# Bluetooth_Mate_4_0.net
KiCad netlist of a schematic drawn in EAGLE
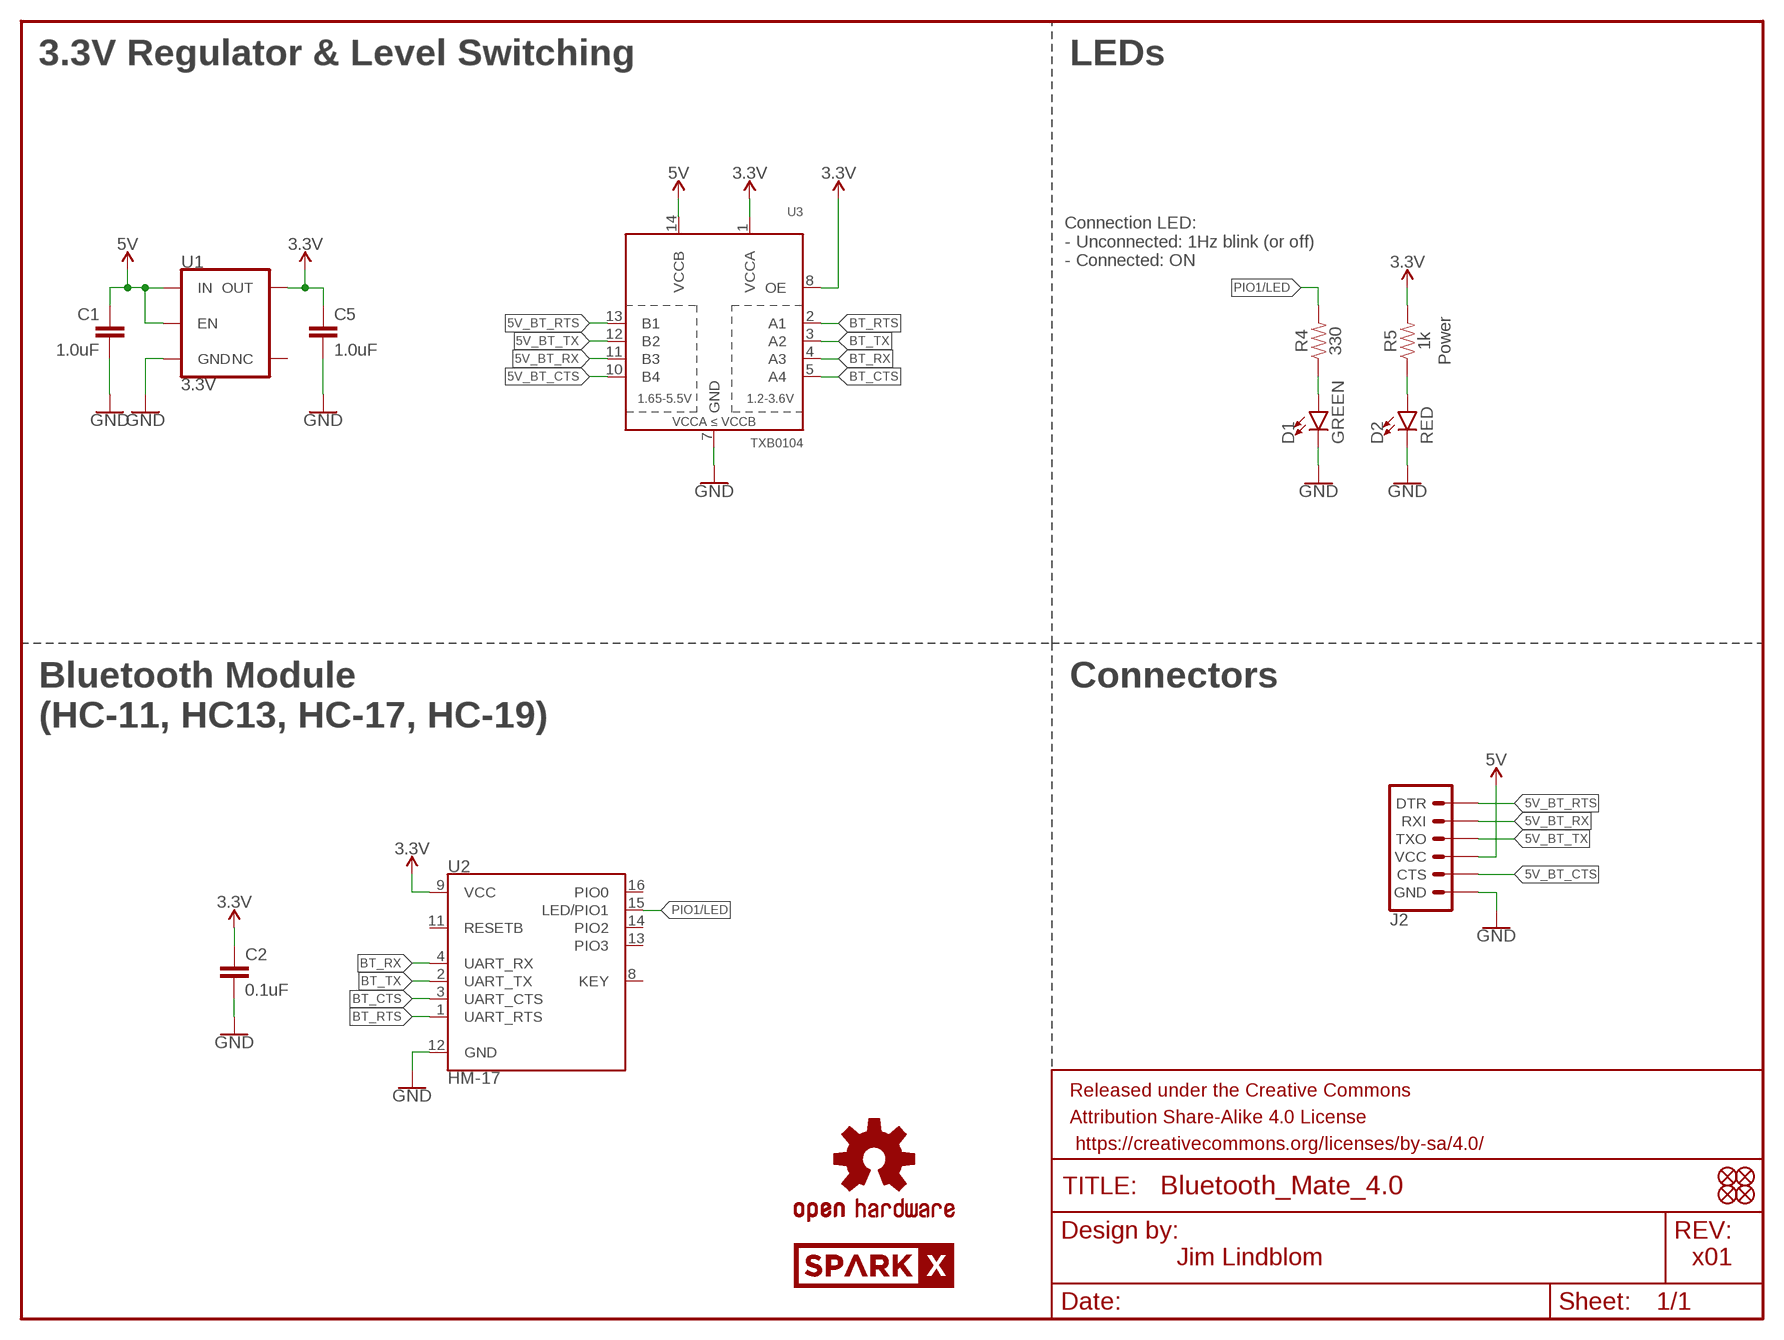
[diagram p0: schematic, sheet 1]

(export (version "E")
  (design (tool "Eeschema 10.0.6"))
  (components
    (comp (ref "C1")
      (value "1.0uF")
      (footprint "eagle-import:0603")
      (libsource (lib "eagle-import") (part "1.0UF-0603-16V-10%"))
    )
    (comp (ref "C2")
      (value "0.1uF")
      (footprint "eagle-import:0603")
      (libsource (lib "eagle-import") (part "0.1UF-0603-25V-(+80/-20%)"))
    )
    (comp (ref "C5")
      (value "1.0uF")
      (footprint "eagle-import:0603")
      (libsource (lib "eagle-import") (part "1.0UF-0603-16V-10%"))
    )
    (comp (ref "D1")
      (value "GREEN")
      (footprint "eagle-import:LED-0603")
      (libsource (lib "eagle-import") (part "LED-GREEN0603"))
    )
    (comp (ref "D2")
      (value "RED")
      (footprint "eagle-import:LED-0603")
      (libsource (lib "eagle-import") (part "LED-RED0603"))
    )
    (comp (ref "FD1")
      (value "FIDUCIALUFIDUCIAL")
      (footprint "eagle-import:FIDUCIAL-MICRO")
      (libsource (lib "eagle-import") (part "FIDUCIALUFIDUCIAL"))
    )
    (comp (ref "FD2")
      (value "FIDUCIALUFIDUCIAL")
      (footprint "eagle-import:FIDUCIAL-MICRO")
      (libsource (lib "eagle-import") (part "FIDUCIALUFIDUCIAL"))
    )
    (comp (ref "FD3")
      (value "FIDUCIALUFIDUCIAL")
      (footprint "eagle-import:FIDUCIAL-MICRO")
      (libsource (lib "eagle-import") (part "FIDUCIALUFIDUCIAL"))
    )
    (comp (ref "FD4")
      (value "FIDUCIALUFIDUCIAL")
      (footprint "eagle-import:FIDUCIAL-MICRO")
      (libsource (lib "eagle-import") (part "FIDUCIALUFIDUCIAL"))
    )
    (comp (ref "FRAME1")
      (value "FRAME-LETTER")
      (footprint "eagle-import:CREATIVE_COMMONS")
      (libsource (lib "eagle-import") (part "FRAME-LETTER"))
    )
    (comp (ref "J2")
      (value "6_PIN_SERIAL_TARGETNO_SILK")
      (footprint "eagle-import:1X06_NO_SILK")
      (libsource (lib "eagle-import") (part "6_PIN_SERIAL_TARGETNO_SILK"))
    )
    (comp (ref "LOGO1")
      (value "OSHW-LOGOMINI")
      (footprint "eagle-import:OSHW-LOGO-MINI")
      (libsource (lib "eagle-import") (part "OSHW-LOGOMINI"))
    )
    (comp (ref "LOGO3")
      (value "SPARKX-LOGO5")
      (footprint "eagle-import:SPARKX-LARGE")
      (libsource (lib "eagle-import") (part "SPARKX-LOGO5"))
    )
    (comp (ref "R4")
      (value "330")
      (footprint "eagle-import:0603")
      (libsource (lib "eagle-import") (part "330OHM-0603-1/10W-1%"))
    )
    (comp (ref "R5")
      (value "1k")
      (footprint "eagle-import:0603")
      (libsource (lib "eagle-import") (part "1KOHM-0603-1/10W-1%"))
    )
    (comp (ref "U1")
      (value "3.3V")
      (footprint "eagle-import:SOT23-5")
      (libsource (lib "eagle-import") (part "V_REG_AP2112K-3.3V"))
    )
    (comp (ref "U2")
      (value "HM-17")
      (footprint "eagle-import:HM-11")
      (libsource (lib "eagle-import") (part "HM-17"))
    )
    (comp (ref "U3")
      (value "TXB0104")
      (footprint "eagle-import:TSSOP14")
      (libsource (lib "eagle-import") (part "TXB0104PWR"))
    )
  )
  (nets
    (net (code "1") (name "3.3V") (class "Default")
      (node (ref "C2") (pin "1") (pinfunction "1_1") (pintype "passive"))
      (node (ref "C5") (pin "1") (pinfunction "1_1") (pintype "passive"))
      (node (ref "R5") (pin "2") (pinfunction "2_2") (pintype "passive"))
      (node (ref "U1") (pin "5") (pinfunction "OUT_5") (pintype "passive"))
      (node (ref "U2") (pin "9") (pinfunction "VCC_9") (pintype "bidirectional"))
      (node (ref "U3") (pin "1") (pinfunction "VCCA_1") (pintype "bidirectional"))
      (node (ref "U3") (pin "8") (pinfunction "OE_8") (pintype "bidirectional"))
    )
    (net (code "2") (name "5V") (class "Default")
      (node (ref "C1") (pin "1") (pinfunction "1_1") (pintype "passive"))
      (node (ref "J2") (pin "4") (pinfunction "VCC_4") (pintype "passive"))
      (node (ref "U1") (pin "1") (pinfunction "IN_1") (pintype "input"))
      (node (ref "U1") (pin "3") (pinfunction "EN_3") (pintype "input"))
      (node (ref "U3") (pin "14") (pinfunction "VCCB_14") (pintype "bidirectional"))
    )
    (net (code "3") (name "5V_BT_CTS") (class "Default")
      (node (ref "J2") (pin "5") (pinfunction "CTS_5") (pintype "passive"))
      (node (ref "U3") (pin "10") (pinfunction "B4_10") (pintype "bidirectional"))
    )
    (net (code "4") (name "5V_BT_RTS") (class "Default")
      (node (ref "J2") (pin "1") (pinfunction "DTR_1") (pintype "passive"))
      (node (ref "U3") (pin "13") (pinfunction "B1_13") (pintype "bidirectional"))
    )
    (net (code "5") (name "5V_BT_RX") (class "Default")
      (node (ref "J2") (pin "2") (pinfunction "RXI_2") (pintype "passive"))
      (node (ref "U3") (pin "11") (pinfunction "B3_11") (pintype "bidirectional"))
    )
    (net (code "6") (name "5V_BT_TX") (class "Default")
      (node (ref "J2") (pin "3") (pinfunction "TXO_3") (pintype "passive"))
      (node (ref "U3") (pin "12") (pinfunction "B2_12") (pintype "bidirectional"))
    )
    (net (code "7") (name "BT_CTS") (class "Default")
      (node (ref "U2") (pin "3") (pinfunction "UART_CTS_3") (pintype "bidirectional"))
      (node (ref "U3") (pin "5") (pinfunction "A4_5") (pintype "bidirectional"))
    )
    (net (code "8") (name "BT_RTS") (class "Default")
      (node (ref "U2") (pin "1") (pinfunction "UART_RTS_1") (pintype "bidirectional"))
      (node (ref "U3") (pin "2") (pinfunction "A1_2") (pintype "bidirectional"))
    )
    (net (code "9") (name "BT_RX") (class "Default")
      (node (ref "U2") (pin "4") (pinfunction "UART_RX_4") (pintype "bidirectional"))
      (node (ref "U3") (pin "4") (pinfunction "A3_4") (pintype "bidirectional"))
    )
    (net (code "10") (name "BT_TX") (class "Default")
      (node (ref "U2") (pin "2") (pinfunction "UART_TX_2") (pintype "bidirectional"))
      (node (ref "U3") (pin "3") (pinfunction "A2_3") (pintype "bidirectional"))
    )
    (net (code "11") (name "GND") (class "Default")
      (node (ref "C1") (pin "2") (pinfunction "2_2") (pintype "passive"))
      (node (ref "C2") (pin "2") (pinfunction "2_2") (pintype "passive"))
      (node (ref "C5") (pin "2") (pinfunction "2_2") (pintype "passive"))
      (node (ref "D1") (pin "C") (pinfunction "C_C") (pintype "passive"))
      (node (ref "D2") (pin "C") (pinfunction "C_C") (pintype "passive"))
      (node (ref "J2") (pin "6") (pinfunction "GND_6") (pintype "passive"))
      (node (ref "U1") (pin "2") (pinfunction "GND_2") (pintype "input"))
      (node (ref "U2") (pin "12") (pinfunction "GND_12") (pintype "bidirectional"))
      (node (ref "U3") (pin "7") (pinfunction "GND_7") (pintype "bidirectional"))
    )
    (net (code "12") (name "Net-(D1-PadA)") (class "Default")
      (node (ref "D1") (pin "A") (pinfunction "A_A") (pintype "passive"))
      (node (ref "R4") (pin "1") (pinfunction "1_1") (pintype "passive"))
    )
    (net (code "13") (name "Net-(D2-PadA)") (class "Default")
      (node (ref "D2") (pin "A") (pinfunction "A_A") (pintype "passive"))
      (node (ref "R5") (pin "1") (pinfunction "1_1") (pintype "passive"))
    )
    (net (code "14") (name "PIO1{slash}LED") (class "Default")
      (node (ref "R4") (pin "2") (pinfunction "2_2") (pintype "passive"))
      (node (ref "U2") (pin "15") (pinfunction "LED/PIO1_15") (pintype "bidirectional"))
    )
    (net (code "15") (name "unconnected-(U1-NC-Pad4)") (class "Default")
      (node (ref "U1") (pin "4") (pinfunction "NC_4") (pintype "no_connect"))
    )
    (net (code "16") (name "unconnected-(U2-KEY-Pad8)") (class "Default")
      (node (ref "U2") (pin "8") (pinfunction "KEY_8") (pintype "bidirectional"))
    )
    (net (code "17") (name "unconnected-(U2-PIO0-Pad16)") (class "Default")
      (node (ref "U2") (pin "16") (pinfunction "PIO0_16") (pintype "bidirectional"))
    )
    (net (code "18") (name "unconnected-(U2-PIO2-Pad14)") (class "Default")
      (node (ref "U2") (pin "14") (pinfunction "PIO2_14") (pintype "bidirectional"))
    )
    (net (code "19") (name "unconnected-(U2-PIO3-Pad13)") (class "Default")
      (node (ref "U2") (pin "13") (pinfunction "PIO3_13") (pintype "bidirectional"))
    )
    (net (code "20") (name "unconnected-(U2-RESETB-Pad11)") (class "Default")
      (node (ref "U2") (pin "11") (pinfunction "RESETB_11") (pintype "bidirectional"))
    )
  )
)
